# MCU098_02_BoosterPack_Connectors.net
KiCad netlist of a schematic drawn in Altium Designer
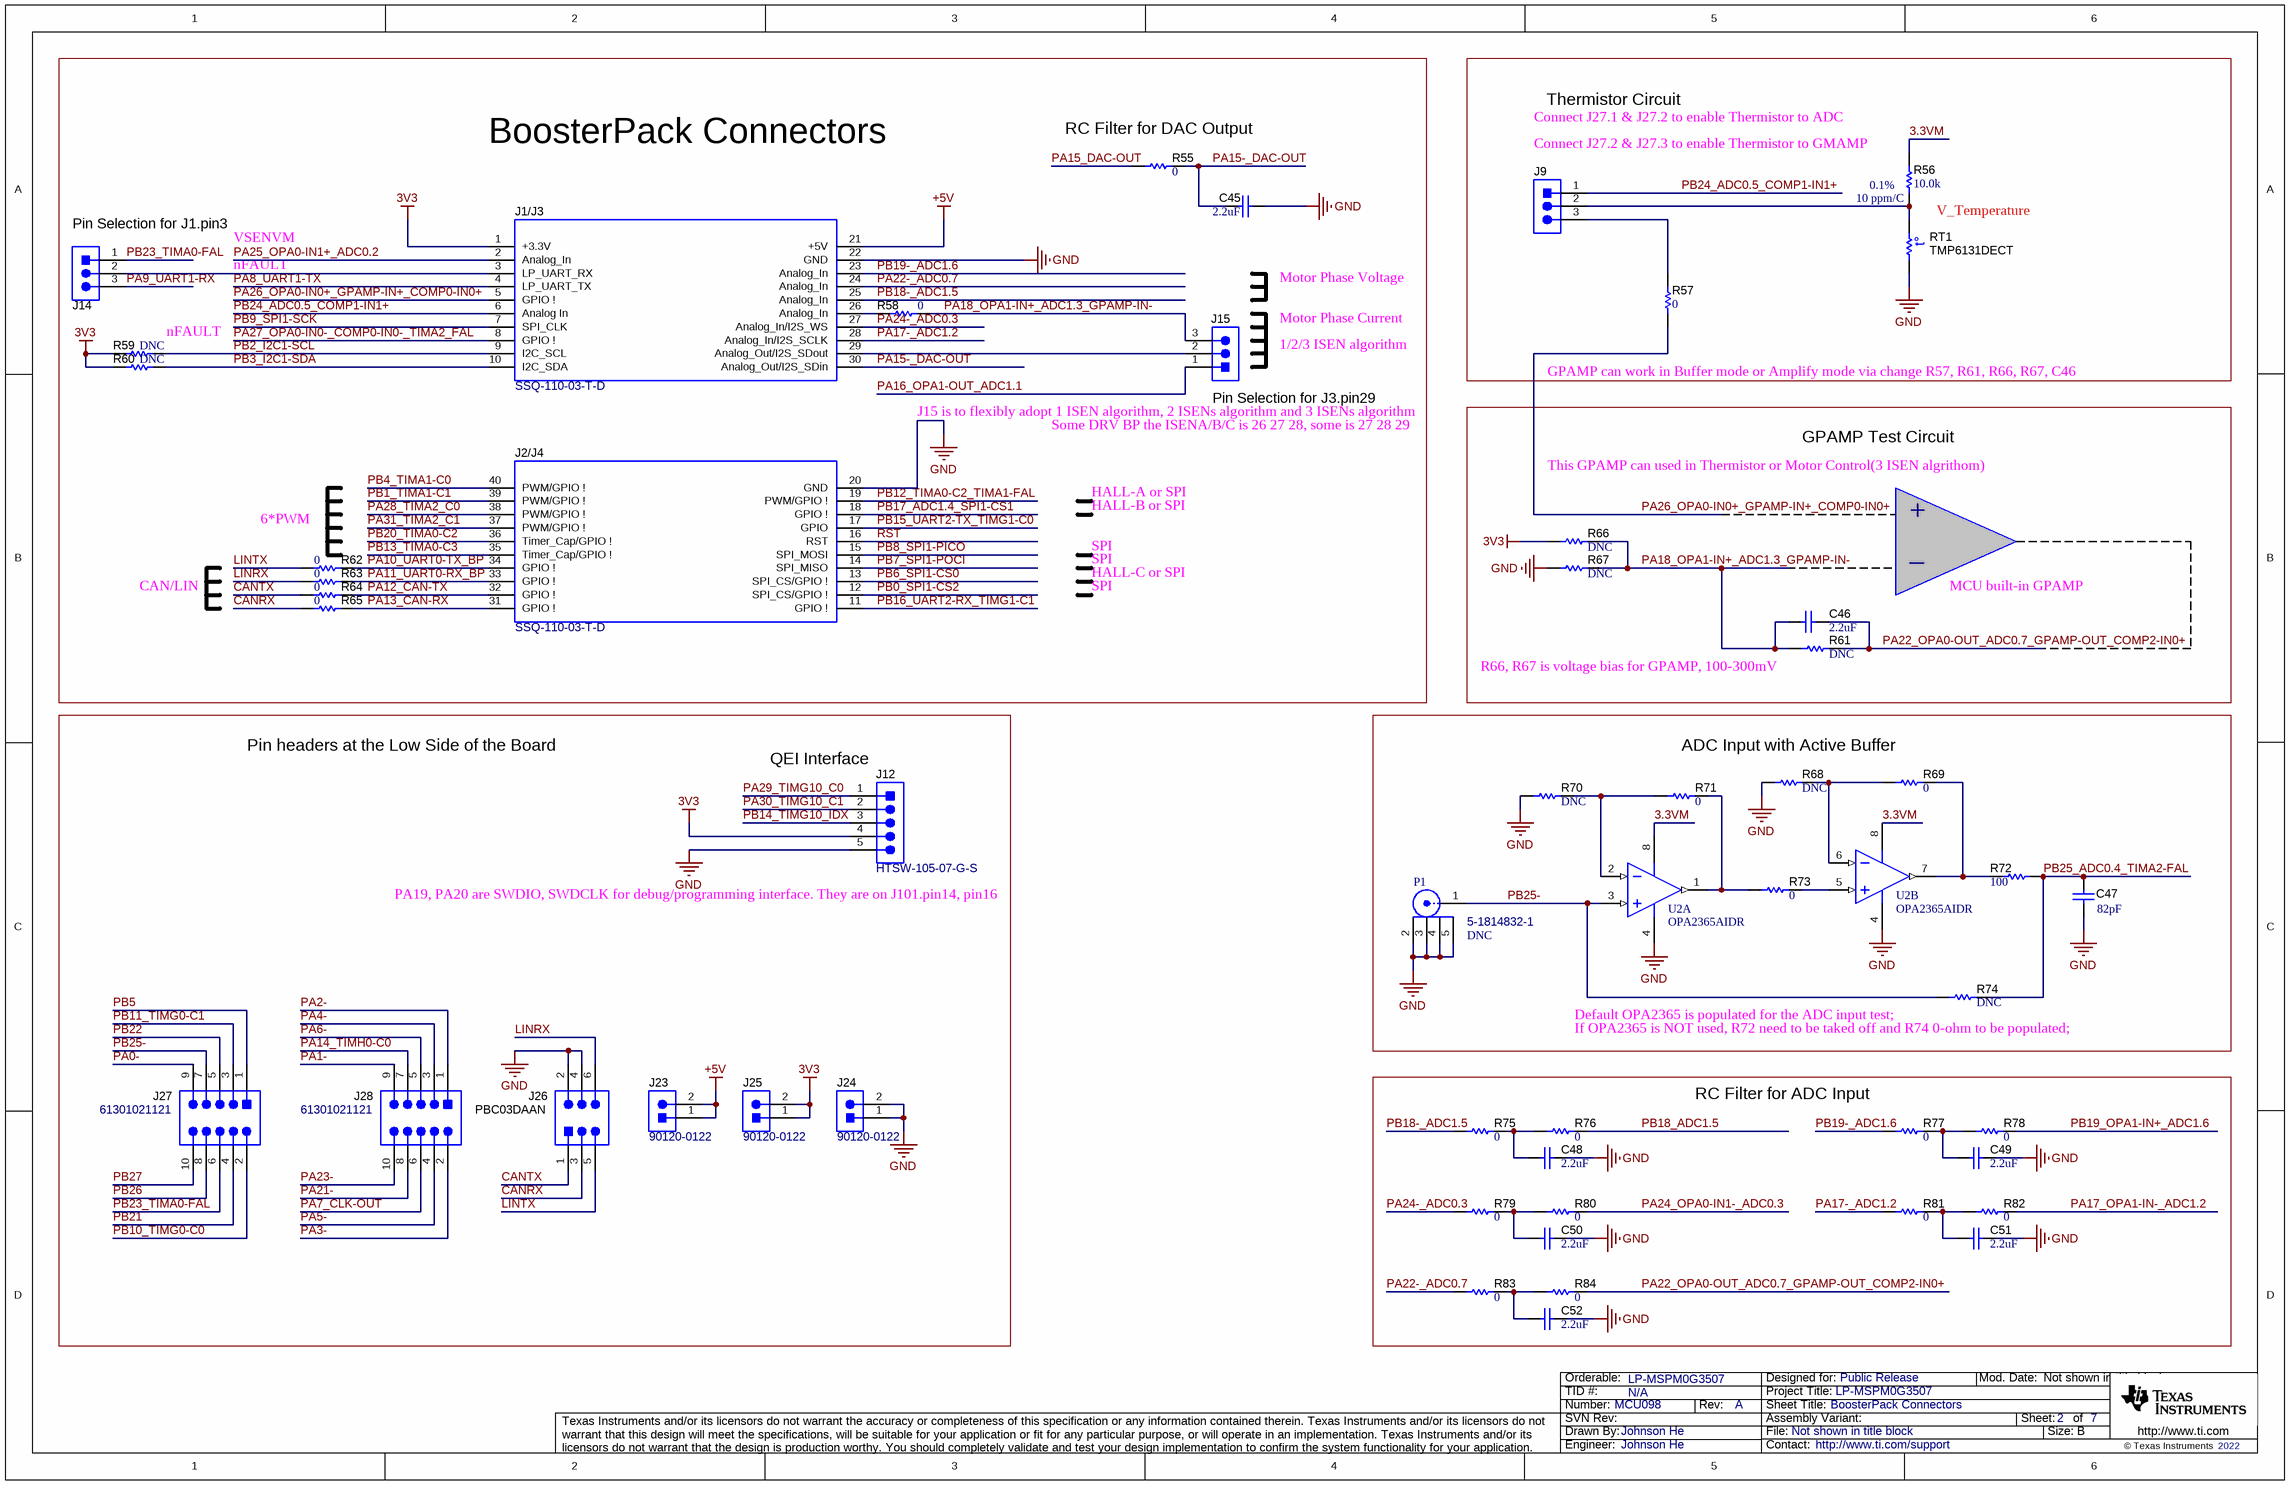
[diagram p0: MCU098_02_BoosterPack_Connectors.SchDoc]

(export (version "E")
  (design (tool "Eeschema 10.0.6"))
  (components
    (comp (ref "C45")
      (value "C0603C225K8PACTU")
      (footprint "0603")
      (description "CAP, CERM, 2.2 uF, 10 V, +/- 10%, X5R, 0603")
      (fields
        (field (name "MANUFACTURER") "Kemet")
        (field (name "VALUEDISPLAYED") "2.2uF")
        (field (name "PUBLISHER") "Texas Instruments")
      )
      (libsource (lib "Altium Vault - TI") (part "Capacitor"))
    )
    (comp (ref "C46")
      (value "C0603C225K8PACTU")
      (footprint "0603")
      (description "CAP, CERM, 2.2 uF, 10 V, +/- 10%, X5R, 0603")
      (fields
        (field (name "MANUFACTURER") "Kemet")
        (field (name "VALUEDISPLAYED") "2.2uF")
        (field (name "PUBLISHER") "Texas Instruments")
      )
      (libsource (lib "Altium Vault - TI") (part "Capacitor"))
    )
    (comp (ref "C47")
      (value "C0603C820K5GACTU")
      (footprint "0603")
      (description "CAP, CERM, 82 pF, 50 V, +/- 10%, C0G/NP0, 0603")
      (fields
        (field (name "MANUFACTURER") "Kemet")
        (field (name "VALUEDISPLAYED") "82pF")
        (field (name "PUBLISHER") "Texas Instruments")
      )
      (libsource (lib "Altium Vault - TI") (part "Capacitor"))
    )
    (comp (ref "C48")
      (value "C0603C225K8PACTU")
      (footprint "0603")
      (description "CAP, CERM, 2.2 uF, 10 V, +/- 10%, X5R, 0603")
      (fields
        (field (name "MANUFACTURER") "Kemet")
        (field (name "VALUEDISPLAYED") "2.2uF")
        (field (name "PUBLISHER") "Texas Instruments")
      )
      (libsource (lib "Altium Vault - TI") (part "Capacitor"))
    )
    (comp (ref "C49")
      (value "C0603C225K8PACTU")
      (footprint "0603")
      (description "CAP, CERM, 2.2 uF, 10 V, +/- 10%, X5R, 0603")
      (fields
        (field (name "MANUFACTURER") "Kemet")
        (field (name "VALUEDISPLAYED") "2.2uF")
        (field (name "PUBLISHER") "Texas Instruments")
      )
      (libsource (lib "Altium Vault - TI") (part "Capacitor"))
    )
    (comp (ref "C50")
      (value "C0603C225K8PACTU")
      (footprint "0603")
      (description "CAP, CERM, 2.2 uF, 10 V, +/- 10%, X5R, 0603")
      (fields
        (field (name "MANUFACTURER") "Kemet")
        (field (name "VALUEDISPLAYED") "2.2uF")
        (field (name "PUBLISHER") "Texas Instruments")
      )
      (libsource (lib "Altium Vault - TI") (part "Capacitor"))
    )
    (comp (ref "C51")
      (value "C0603C225K8PACTU")
      (footprint "0603")
      (description "CAP, CERM, 2.2 uF, 10 V, +/- 10%, X5R, 0603")
      (fields
        (field (name "MANUFACTURER") "Kemet")
        (field (name "VALUEDISPLAYED") "2.2uF")
        (field (name "PUBLISHER") "Texas Instruments")
      )
      (libsource (lib "Altium Vault - TI") (part "Capacitor"))
    )
    (comp (ref "C52")
      (value "C0603C225K8PACTU")
      (footprint "0603")
      (description "CAP, CERM, 2.2 uF, 10 V, +/- 10%, X5R, 0603")
      (fields
        (field (name "MANUFACTURER") "Kemet")
        (field (name "VALUEDISPLAYED") "2.2uF")
        (field (name "PUBLISHER") "Texas Instruments")
      )
      (libsource (lib "Altium Vault - TI") (part "Capacitor"))
    )
    (comp (ref "J1/J3")
      (value "SSQ-110-03-T-D")
      (footprint "BoosterPack_40pin_J1J3")
      (description "Receptacle, 2.54mm, 10x2, Tin, TH")
      (fields (field (name "ALTERNATE PARTNUMBER") "CRD-081413-A-G") (field (name "MANUFACTURER") "Samtec"))
      (libsource (lib "Altium Vault - TI") (part "BoosterPack_40pin_J1J3"))
    )
    (comp (ref "J2/J4")
      (value "SSQ-110-03-T-D")
      (footprint "BoosterPack_40pin_J2J4")
      (description "Receptacle, 2.54mm, 10x2, Tin, TH")
      (fields (field (name "ALTERNATE PARTNUMBER") "CRD-081413-A-G") (field (name "MANUFACTURER") "Samtec"))
      (libsource (lib "Altium Vault - TI") (part "BoosterPack_40pin_J2J4"))
    )
    (comp (ref "J9")
      (value "PEC03SAAN")
      (footprint "CONN_PEC03SAAN")
      (description "Header, 100mil, 3x1, Tin, TH")
      (fields
        (field (name "MANUFACTURER") "Sullins Connector Solutions")
        (field (name "PUBLISHER") "Texas Instruments")
      )
      (libsource (lib "") (part "Header_3x1_Launchpad_1"))
    )
    (comp (ref "J12")
      (value "HTSW-105-07-G-S")
      (footprint "Samtec_HTSW-105-07-G-S")
      (description "Header, 100mil, 5x1, Gold, TH")
      (fields (field (name "MANUFACTURER") "Samtec") (field (name "PUBLISHER") "Texas Instruments"))
      (libsource (lib "Altium Vault - TI") (part "Header_5x1"))
    )
    (comp (ref "J14")
      (value "PEC03SAAN")
      (footprint "CONN_PEC03SAAN")
      (description "Header, 100mil, 3x1, Tin, TH")
      (fields
        (field (name "MANUFACTURER") "Sullins Connector Solutions")
        (field (name "PUBLISHER") "Texas Instruments")
      )
      (libsource (lib "") (part "Header_3x1_Launchpad_1"))
    )
    (comp (ref "J15")
      (value "PEC03SAAN")
      (footprint "CONN_PEC03SAAN")
      (description "Header, 100mil, 3x1, Tin, TH")
      (fields
        (field (name "MANUFACTURER") "Sullins Connector Solutions")
        (field (name "PUBLISHER") "Texas Instruments")
      )
      (libsource (lib "Altium Vault - TI") (part "Header_3x1_Launchpad"))
    )
    (comp (ref "J23")
      (value "90120-0122")
      (footprint "CONN_90120-0122")
      (description "Header, 100mil, 2x1, Tin, TH")
      (fields (field (name "MANUFACTURER") "Molex") (field (name "PUBLISHER") "Texas Instruments"))
      (libsource (lib "Altium Vault - TI") (part "Header_2x1"))
    )
    (comp (ref "J24")
      (value "90120-0122")
      (footprint "CONN_90120-0122")
      (description "Header, 100mil, 2x1, Tin, TH")
      (fields (field (name "MANUFACTURER") "Molex") (field (name "PUBLISHER") "Texas Instruments"))
      (libsource (lib "Altium Vault - TI") (part "Header_2x1"))
    )
    (comp (ref "J25")
      (value "90120-0122")
      (footprint "CONN_90120-0122")
      (description "Header, 100mil, 2x1, Tin, TH")
      (fields (field (name "MANUFACTURER") "Molex") (field (name "PUBLISHER") "Texas Instruments"))
      (libsource (lib "Altium Vault - TI") (part "Header_2x1"))
    )
    (comp (ref "J26")
      (value "PBC03DAAN")
      (footprint "Sullins_PBC03DAAN")
      (description "Header, 100mil, 3x2, Gold, TH")
      (fields (field (name "MANUFACTURER") "Sullins Connector Solutions"))
      (libsource (lib "Altium Vault - TI") (part "Header_3x2"))
    )
    (comp (ref "J27")
      (value "61301021121")
      (footprint "WURTH_61301021121")
      (description "Header, 2.54 mm, 5x2, Gold, TH")
      (fields (field (name "MANUFACTURER") "Wurth Elektronik"))
      (libsource (lib "Altium Vault - TI") (part "Header_5x2"))
    )
    (comp (ref "J28")
      (value "61301021121")
      (footprint "WURTH_61301021121")
      (description "Header, 2.54 mm, 5x2, Gold, TH")
      (fields (field (name "MANUFACTURER") "Wurth Elektronik"))
      (libsource (lib "Altium Vault - TI") (part "Header_5x2"))
    )
    (comp (ref "P1")
      (value "5-1814832-1")
      (footprint "TE_5-1814832-1")
      (description "SMA Straight PCB Socket Die Cast, 50 Ohm, TH")
      (fields
        (field (name "MANUFACTURER") "TE Connectivity")
        (field (name "VALUEDISPLAYED") "DNC")
        (field (name "PUBLISHER") "Texas Instruments")
      )
      (libsource (lib "Altium Vault - TI") (part "SMA_Contact1_GND2345"))
    )
    (comp (ref "R55")
      (value "RC0603JR-070RL")
      (footprint "0603")
      (description "RES, 0, 5%, 0.1 W, 0603")
      (fields (field (name "MANUFACTURER") "Yageo") (field (name "VALUEDISPLAYED") "0"))
      (libsource (lib "Altium Vault - TI") (part "Resistor"))
    )
    (comp (ref "R56")
      (value "ERA3ARB103V")
      (footprint "ERA3A")
      (description "RES, 10.0 k, 0.1%, 0.1 W, AEC-Q200 Grade 0, 1.6x0.8mm")
      (fields
        (field (name "TOLERANCE_%") "0.1%")
        (field (name "MANUFACTURER") "Panasonic")
        (field (name "TEMPCO") "10 ppm/C")
        (field (name "VALUEDISPLAYED") "10.0k")
      )
      (libsource (lib "Altium Vault - TI") (part "Resistor"))
    )
    (comp (ref "R57")
      (value "RC0603JR-070RL")
      (footprint "0603")
      (description "RES, 0, 5%, 0.1 W, 0603")
      (fields (field (name "MANUFACTURER") "Yageo") (field (name "VALUEDISPLAYED") "0"))
      (libsource (lib "Altium Vault - TI") (part "Resistor"))
    )
    (comp (ref "R58")
      (value "RC0603JR-070RL")
      (footprint "0603")
      (description "RES, 0, 5%, 0.1 W, 0603")
      (fields (field (name "MANUFACTURER") "Yageo") (field (name "VALUEDISPLAYED") "0"))
      (libsource (lib "Altium Vault - TI") (part "Resistor"))
    )
    (comp (ref "R59")
      (value "CRCW04024K70JNED")
      (footprint "0402")
      (description "RES, 4.7 k, 5%, 0.063 W, AEC-Q200 Grade 0, 0402")
      (fields (field (name "MANUFACTURER") "Vishay-Dale") (field (name "VALUEDISPLAYED") "DNC"))
      (libsource (lib "Altium Vault - TI") (part "Resistor"))
    )
    (comp (ref "R60")
      (value "CRCW04024K70JNED")
      (footprint "0402")
      (description "RES, 4.7 k, 5%, 0.063 W, AEC-Q200 Grade 0, 0402")
      (fields (field (name "MANUFACTURER") "Vishay-Dale") (field (name "VALUEDISPLAYED") "DNC"))
      (libsource (lib "Altium Vault - TI") (part "Resistor"))
    )
    (comp (ref "R61")
      (value "RC0603JR-070RL")
      (footprint "0603")
      (description "RES, 0, 5%, 0.1 W, 0603")
      (fields (field (name "MANUFACTURER") "Yageo") (field (name "VALUEDISPLAYED") "DNC"))
      (libsource (lib "Altium Vault - TI") (part "Resistor"))
    )
    (comp (ref "R62")
      (value "RC0603JR-070RL")
      (footprint "0603")
      (description "RES, 0, 5%, 0.1 W, 0603")
      (fields (field (name "MANUFACTURER") "Yageo") (field (name "VALUEDISPLAYED") "0"))
      (libsource (lib "Altium Vault - TI") (part "Resistor"))
    )
    (comp (ref "R63")
      (value "RC0603JR-070RL")
      (footprint "0603")
      (description "RES, 0, 5%, 0.1 W, 0603")
      (fields (field (name "MANUFACTURER") "Yageo") (field (name "VALUEDISPLAYED") "0"))
      (libsource (lib "Altium Vault - TI") (part "Resistor"))
    )
    (comp (ref "R64")
      (value "RC0603JR-070RL")
      (footprint "0603")
      (description "RES, 0, 5%, 0.1 W, 0603")
      (fields (field (name "MANUFACTURER") "Yageo") (field (name "VALUEDISPLAYED") "0"))
      (libsource (lib "Altium Vault - TI") (part "Resistor"))
    )
    (comp (ref "R65")
      (value "RC0603JR-070RL")
      (footprint "0603")
      (description "RES, 0, 5%, 0.1 W, 0603")
      (fields (field (name "MANUFACTURER") "Yageo") (field (name "VALUEDISPLAYED") "0"))
      (libsource (lib "Altium Vault - TI") (part "Resistor"))
    )
    (comp (ref "R66")
      (value "RC0603JR-070RL")
      (footprint "0603")
      (description "RES, 0, 5%, 0.1 W, 0603")
      (fields (field (name "MANUFACTURER") "Yageo") (field (name "VALUEDISPLAYED") "DNC"))
      (libsource (lib "Altium Vault - TI") (part "Resistor"))
    )
    (comp (ref "R67")
      (value "RC0603JR-070RL")
      (footprint "0603")
      (description "RES, 0, 5%, 0.1 W, 0603")
      (fields (field (name "MANUFACTURER") "Yageo") (field (name "VALUEDISPLAYED") "DNC"))
      (libsource (lib "Altium Vault - TI") (part "Resistor"))
    )
    (comp (ref "R68")
      (value "RC0603JR-070RL")
      (footprint "0603")
      (description "RES, 0, 5%, 0.1 W, 0603")
      (fields (field (name "MANUFACTURER") "Yageo") (field (name "VALUEDISPLAYED") "DNC"))
      (libsource (lib "Altium Vault - TI") (part "Resistor"))
    )
    (comp (ref "R69")
      (value "RC0603JR-070RL")
      (footprint "0603")
      (description "RES, 0, 5%, 0.1 W, 0603")
      (fields (field (name "MANUFACTURER") "Yageo") (field (name "VALUEDISPLAYED") "0"))
      (libsource (lib "Altium Vault - TI") (part "Resistor"))
    )
    (comp (ref "R70")
      (value "RC0603JR-070RL")
      (footprint "0603")
      (description "RES, 0, 5%, 0.1 W, 0603")
      (fields (field (name "MANUFACTURER") "Yageo") (field (name "VALUEDISPLAYED") "DNC"))
      (libsource (lib "Altium Vault - TI") (part "Resistor"))
    )
    (comp (ref "R71")
      (value "RC0603JR-070RL")
      (footprint "0603")
      (description "RES, 0, 5%, 0.1 W, 0603")
      (fields (field (name "MANUFACTURER") "Yageo") (field (name "VALUEDISPLAYED") "0"))
      (libsource (lib "Altium Vault - TI") (part "Resistor"))
    )
    (comp (ref "R72")
      (value "RC0603FR-07100RL")
      (footprint "0603")
      (description "RES, 100, 1%, 0.1 W, 0603")
      (fields (field (name "MANUFACTURER") "Yageo") (field (name "VALUEDISPLAYED") "100"))
      (libsource (lib "Altium Vault - TI") (part "Resistor"))
    )
    (comp (ref "R73")
      (value "RC0603JR-070RL")
      (footprint "0603")
      (description "RES, 0, 5%, 0.1 W, 0603")
      (fields (field (name "MANUFACTURER") "Yageo") (field (name "VALUEDISPLAYED") "0"))
      (libsource (lib "Altium Vault - TI") (part "Resistor"))
    )
    (comp (ref "R74")
      (value "RC0603JR-070RL")
      (footprint "0603")
      (description "RES, 0, 5%, 0.1 W, 0603")
      (fields (field (name "MANUFACTURER") "Yageo") (field (name "VALUEDISPLAYED") "DNC"))
      (libsource (lib "Altium Vault - TI") (part "Resistor"))
    )
    (comp (ref "R75")
      (value "RC0603JR-070RL")
      (footprint "0603")
      (description "RES, 0, 5%, 0.1 W, 0603")
      (fields (field (name "MANUFACTURER") "Yageo") (field (name "VALUEDISPLAYED") "0"))
      (libsource (lib "Altium Vault - TI") (part "Resistor"))
    )
    (comp (ref "R76")
      (value "RC0603JR-070RL")
      (footprint "0603")
      (description "RES, 0, 5%, 0.1 W, 0603")
      (fields (field (name "MANUFACTURER") "Yageo") (field (name "VALUEDISPLAYED") "0"))
      (libsource (lib "Altium Vault - TI") (part "Resistor"))
    )
    (comp (ref "R77")
      (value "RC0603JR-070RL")
      (footprint "0603")
      (description "RES, 0, 5%, 0.1 W, 0603")
      (fields (field (name "MANUFACTURER") "Yageo") (field (name "VALUEDISPLAYED") "0"))
      (libsource (lib "Altium Vault - TI") (part "Resistor"))
    )
    (comp (ref "R78")
      (value "RC0603JR-070RL")
      (footprint "0603")
      (description "RES, 0, 5%, 0.1 W, 0603")
      (fields (field (name "MANUFACTURER") "Yageo") (field (name "VALUEDISPLAYED") "0"))
      (libsource (lib "Altium Vault - TI") (part "Resistor"))
    )
    (comp (ref "R79")
      (value "RC0603JR-070RL")
      (footprint "0603")
      (description "RES, 0, 5%, 0.1 W, 0603")
      (fields (field (name "MANUFACTURER") "Yageo") (field (name "VALUEDISPLAYED") "0"))
      (libsource (lib "Altium Vault - TI") (part "Resistor"))
    )
    (comp (ref "R80")
      (value "RC0603JR-070RL")
      (footprint "0603")
      (description "RES, 0, 5%, 0.1 W, 0603")
      (fields (field (name "MANUFACTURER") "Yageo") (field (name "VALUEDISPLAYED") "0"))
      (libsource (lib "Altium Vault - TI") (part "Resistor"))
    )
    (comp (ref "R81")
      (value "RC0603JR-070RL")
      (footprint "0603")
      (description "RES, 0, 5%, 0.1 W, 0603")
      (fields (field (name "MANUFACTURER") "Yageo") (field (name "VALUEDISPLAYED") "0"))
      (libsource (lib "Altium Vault - TI") (part "Resistor"))
    )
    (comp (ref "R82")
      (value "RC0603JR-070RL")
      (footprint "0603")
      (description "RES, 0, 5%, 0.1 W, 0603")
      (fields (field (name "MANUFACTURER") "Yageo") (field (name "VALUEDISPLAYED") "0"))
      (libsource (lib "Altium Vault - TI") (part "Resistor"))
    )
    (comp (ref "R83")
      (value "RC0603JR-070RL")
      (footprint "0603")
      (description "RES, 0, 5%, 0.1 W, 0603")
      (fields (field (name "MANUFACTURER") "Yageo") (field (name "VALUEDISPLAYED") "0"))
      (libsource (lib "Altium Vault - TI") (part "Resistor"))
    )
    (comp (ref "R84")
      (value "RC0603JR-070RL")
      (footprint "0603")
      (description "RES, 0, 5%, 0.1 W, 0603")
      (fields (field (name "MANUFACTURER") "Yageo") (field (name "VALUEDISPLAYED") "0"))
      (libsource (lib "Altium Vault - TI") (part "Resistor"))
    )
    (comp (ref "RT1")
      (value "TMP6131DECT")
      (footprint "DEC0002A")
      (description "Thermistor, DEC0002A (X1SON-2)")
      (fields
        (field (name "ALTERNATE PARTNUMBER") "TMP6131DECR")
        (field (name "PARTNUMBER") "TMP6131DECT")
        (field (name "MANUFACTURER") "Texas Instruments")
      )
      (libsource (lib "Altium Vault - TI") (part "Thermistor"))
    )
    (comp (ref "U2")
      (value "OPA2365AIDR")
      (footprint "D0008A_L")
      (fields (field (name "MANUFACTURER") "Texas Instruments") (field (name "PARTNUMBER") "OPA2365AIDR"))
      (libsource (lib "Altium Vault - TI") (part "TI-OPA2365D8"))
    )
  )
  (nets
    (net (code "1") (name "+5V") (class "Default")
      (node (ref "J1/J3") (pin "21") (pinfunction "+5V_21") (pintype "power_in"))
      (node (ref "J23") (pin "1") (pinfunction "1_1") (pintype "passive"))
      (node (ref "J23") (pin "2") (pinfunction "2_2") (pintype "passive"))
    )
    (net (code "2") (name "/3.3VM") (class "Default")
      (node (ref "R56") (pin "2") (pinfunction "2_2") (pintype "passive"))
      (node (ref "U2") (pin "8") (pinfunction "V+_8") (pintype "power_in"))
    )
    (net (code "3") (name "/CANRX") (class "Default")
      (node (ref "J26") (pin "3") (pinfunction "3_3") (pintype "passive"))
      (node (ref "R65") (pin "1") (pinfunction "1_1") (pintype "passive"))
    )
    (net (code "4") (name "/CANTX") (class "Default")
      (node (ref "J26") (pin "1") (pinfunction "1_1") (pintype "passive"))
      (node (ref "R64") (pin "1") (pinfunction "1_1") (pintype "passive"))
    )
    (net (code "5") (name "/LINRX") (class "Default")
      (node (ref "J26") (pin "6") (pinfunction "6_6") (pintype "passive"))
      (node (ref "R63") (pin "1") (pinfunction "1_1") (pintype "passive"))
    )
    (net (code "6") (name "/LINTX") (class "Default")
      (node (ref "J26") (pin "5") (pinfunction "5_5") (pintype "passive"))
      (node (ref "R62") (pin "1") (pinfunction "1_1") (pintype "passive"))
    )
    (net (code "7") (name "/PA0-") (class "Default")
      (node (ref "J27") (pin "9") (pinfunction "9_9") (pintype "passive"))
    )
    (net (code "8") (name "/PA1-") (class "Default")
      (node (ref "J28") (pin "9") (pinfunction "9_9") (pintype "passive"))
    )
    (net (code "9") (name "/PA2-") (class "Default")
      (node (ref "J28") (pin "1") (pinfunction "1_1") (pintype "passive"))
    )
    (net (code "10") (name "/PA3-") (class "Default")
      (node (ref "J28") (pin "2") (pinfunction "2_2") (pintype "passive"))
    )
    (net (code "11") (name "/PA4-") (class "Default")
      (node (ref "J28") (pin "3") (pinfunction "3_3") (pintype "passive"))
    )
    (net (code "12") (name "/PA5-") (class "Default")
      (node (ref "J28") (pin "4") (pinfunction "4_4") (pintype "passive"))
    )
    (net (code "13") (name "/PA6-") (class "Default")
      (node (ref "J28") (pin "5") (pinfunction "5_5") (pintype "passive"))
    )
    (net (code "14") (name "/PA7_CLK-OUT") (class "Default")
      (node (ref "J28") (pin "6") (pinfunction "6_6") (pintype "passive"))
    )
    (net (code "15") (name "/PA8_UART1-TX") (class "Default")
      (node (ref "J1/J3") (pin "4") (pinfunction "LP_UART_TX_4") (pintype "passive"))
    )
    (net (code "16") (name "/PA9_UART1-RX") (class "Default")
      (node (ref "J14") (pin "3") (pinfunction "3_3") (pintype "passive"))
    )
    (net (code "17") (name "/PA10_UART0-TX_BP") (class "Default")
      (node (ref "J2/J4") (pin "34") (pinfunction "GPIO_!_34") (pintype "passive"))
      (node (ref "R62") (pin "2") (pinfunction "2_2") (pintype "passive"))
    )
    (net (code "18") (name "/PA11_UART0-RX_BP") (class "Default")
      (node (ref "J2/J4") (pin "33") (pinfunction "GPIO_!_33") (pintype "passive"))
      (node (ref "R63") (pin "2") (pinfunction "2_2") (pintype "passive"))
    )
    (net (code "19") (name "/PA12_CAN-TX") (class "Default")
      (node (ref "J2/J4") (pin "32") (pinfunction "GPIO_!_32") (pintype "passive"))
      (node (ref "R64") (pin "2") (pinfunction "2_2") (pintype "passive"))
    )
    (net (code "20") (name "/PA13_CAN-RX") (class "Default")
      (node (ref "J2/J4") (pin "31") (pinfunction "GPIO_!_31") (pintype "passive"))
      (node (ref "R65") (pin "2") (pinfunction "2_2") (pintype "passive"))
    )
    (net (code "21") (name "/PA14_TIMH0-C0") (class "Default")
      (node (ref "J28") (pin "7") (pinfunction "7_7") (pintype "passive"))
    )
    (net (code "22") (name "/PA15-_DAC-OUT") (class "Default")
      (node (ref "C45") (pin "1") (pinfunction "1_1") (pintype "passive"))
      (node (ref "J1/J3") (pin "30") (pinfunction "Analog_Out/I2S_SDin_30") (pintype "passive"))
      (node (ref "R55") (pin "2") (pinfunction "2_2") (pintype "passive"))
    )
    (net (code "23") (name "/PA15_DAC-OUT") (class "Default")
      (node (ref "R55") (pin "1") (pinfunction "1_1") (pintype "passive"))
    )
    (net (code "24") (name "/PA16_OPA1-OUT_ADC1.1") (class "Default")
      (node (ref "J15") (pin "1") (pinfunction "1_1") (pintype "passive"))
    )
    (net (code "25") (name "/PA17-_ADC1.2") (class "Default")
      (node (ref "J1/J3") (pin "28") (pinfunction "Analog_In/I2S_SCLK_28") (pintype "passive"))
      (node (ref "R81") (pin "1") (pinfunction "1_1") (pintype "passive"))
    )
    (net (code "26") (name "/PA17_OPA1-IN-_ADC1.2") (class "Default")
      (node (ref "R82") (pin "2") (pinfunction "2_2") (pintype "passive"))
    )
    (net (code "27") (name "/PA18_OPA1-IN+_ADC1.3_GPAMP-IN-") (class "Default")
      (node (ref "C46") (pin "1") (pinfunction "1_1") (pintype "passive"))
      (node (ref "J15") (pin "3") (pinfunction "3_3") (pintype "passive"))
      (node (ref "R58") (pin "2") (pinfunction "2_2") (pintype "passive"))
      (node (ref "R61") (pin "1") (pinfunction "1_1") (pintype "passive"))
      (node (ref "R66") (pin "2") (pinfunction "2_2") (pintype "passive"))
      (node (ref "R67") (pin "2") (pinfunction "2_2") (pintype "passive"))
    )
    (net (code "28") (name "/PA21-") (class "Default")
      (node (ref "J28") (pin "8") (pinfunction "8_8") (pintype "passive"))
    )
    (net (code "29") (name "/PA22-_ADC0.7") (class "Default")
      (node (ref "J1/J3") (pin "24") (pinfunction "Analog_In_24") (pintype "passive"))
      (node (ref "R83") (pin "1") (pinfunction "1_1") (pintype "passive"))
    )
    (net (code "30") (name "/PA22_OPA0-OUT_ADC0.7_GPAMP-OUT_COMP2-IN0+") (class "Default")
      (node (ref "C46") (pin "2") (pinfunction "2_2") (pintype "passive"))
      (node (ref "R61") (pin "2") (pinfunction "2_2") (pintype "passive"))
      (node (ref "R84") (pin "2") (pinfunction "2_2") (pintype "passive"))
    )
    (net (code "31") (name "/PA23-") (class "Default")
      (node (ref "J28") (pin "10") (pinfunction "10_10") (pintype "passive"))
    )
    (net (code "32") (name "/PA24-_ADC0.3") (class "Default")
      (node (ref "J1/J3") (pin "27") (pinfunction "Analog_In/I2S_WS_27") (pintype "passive"))
      (node (ref "R79") (pin "1") (pinfunction "1_1") (pintype "passive"))
    )
    (net (code "33") (name "/PA24_OPA0-IN1-_ADC0.3") (class "Default")
      (node (ref "R80") (pin "2") (pinfunction "2_2") (pintype "passive"))
    )
    (net (code "34") (name "/PA25_OPA0-IN1+_ADC0.2") (class "Default")
      (node (ref "J1/J3") (pin "2") (pinfunction "Analog_In_2") (pintype "passive"))
    )
    (net (code "35") (name "/PA26_OPA0-IN0+_GPAMP-IN+_COMP0-IN0+") (class "Default")
      (node (ref "J1/J3") (pin "5") (pinfunction "GPIO_!_5") (pintype "passive"))
      (node (ref "R57") (pin "1") (pinfunction "1_1") (pintype "passive"))
    )
    (net (code "36") (name "/PA27_OPA0-IN0-_COMP0-IN0-_TIMA2_FAL") (class "Default")
      (node (ref "J1/J3") (pin "8") (pinfunction "GPIO_!_8") (pintype "passive"))
    )
    (net (code "37") (name "/PA28_TIMA2_C0") (class "Default")
      (node (ref "J2/J4") (pin "38") (pinfunction "PWM/GPIO_!_38") (pintype "passive"))
    )
    (net (code "38") (name "/PA29_TIMG10_C0") (class "Default")
      (node (ref "J12") (pin "1") (pinfunction "1_1") (pintype "passive"))
    )
    (net (code "39") (name "/PA30_TIMG10_C1") (class "Default")
      (node (ref "J12") (pin "2") (pinfunction "2_2") (pintype "passive"))
    )
    (net (code "40") (name "/PA31_TIMA2_C1") (class "Default")
      (node (ref "J2/J4") (pin "37") (pinfunction "PWM/GPIO_!_37") (pintype "passive"))
    )
    (net (code "41") (name "/PB0_SPI1-CS2") (class "Default")
      (node (ref "J2/J4") (pin "12") (pinfunction "SPI_CS/GPIO_!_12") (pintype "passive"))
    )
    (net (code "42") (name "/PB1_TIMA1-C1") (class "Default")
      (node (ref "J2/J4") (pin "39") (pinfunction "PWM/GPIO_!_39") (pintype "passive"))
    )
    (net (code "43") (name "/PB2_I2C1-SCL") (class "Default")
      (node (ref "J1/J3") (pin "9") (pinfunction "I2C_SCL_9") (pintype "passive"))
      (node (ref "R59") (pin "2") (pinfunction "2_2") (pintype "passive"))
    )
    (net (code "44") (name "/PB3_I2C1-SDA") (class "Default")
      (node (ref "J1/J3") (pin "10") (pinfunction "I2C_SDA_10") (pintype "passive"))
      (node (ref "R60") (pin "2") (pinfunction "2_2") (pintype "passive"))
    )
    (net (code "45") (name "/PB4_TIMA1-C0") (class "Default")
      (node (ref "J2/J4") (pin "40") (pinfunction "PWM/GPIO_!_40") (pintype "passive"))
    )
    (net (code "46") (name "/PB5") (class "Default")
      (node (ref "J27") (pin "1") (pinfunction "1_1") (pintype "passive"))
    )
    (net (code "47") (name "/PB6_SPI1-CS0") (class "Default")
      (node (ref "J2/J4") (pin "13") (pinfunction "SPI_CS/GPIO_!_13") (pintype "passive"))
    )
    (net (code "48") (name "/PB7_SPI1-POCI") (class "Default")
      (node (ref "J2/J4") (pin "14") (pinfunction "SPI_MISO_14") (pintype "passive"))
    )
    (net (code "49") (name "/PB8_SPI1-PICO") (class "Default")
      (node (ref "J2/J4") (pin "15") (pinfunction "SPI_MOSI_15") (pintype "passive"))
    )
    (net (code "50") (name "/PB9_SPI1-SCK") (class "Default")
      (node (ref "J1/J3") (pin "7") (pinfunction "SPI_CLK_7") (pintype "passive"))
    )
    (net (code "51") (name "/PB10_TIMG0-C0") (class "Default")
      (node (ref "J27") (pin "2") (pinfunction "2_2") (pintype "passive"))
    )
    (net (code "52") (name "/PB11_TIMG0-C1") (class "Default")
      (node (ref "J27") (pin "3") (pinfunction "3_3") (pintype "passive"))
    )
    (net (code "53") (name "/PB12_TIMA0-C2_TIMA1-FAL") (class "Default")
      (node (ref "J2/J4") (pin "19") (pinfunction "PWM/GPIO_!_19") (pintype "passive"))
    )
    (net (code "54") (name "/PB13_TIMA0-C3") (class "Default")
      (node (ref "J2/J4") (pin "35") (pinfunction "Timer_Cap/GPIO_!_35") (pintype "passive"))
    )
    (net (code "55") (name "/PB14_TIMG10_IDX") (class "Default")
      (node (ref "J12") (pin "3") (pinfunction "3_3") (pintype "passive"))
    )
    (net (code "56") (name "/PB15_UART2-TX_TIMG1-C0") (class "Default")
      (node (ref "J2/J4") (pin "17") (pinfunction "GPIO_17") (pintype "passive"))
    )
    (net (code "57") (name "/PB16_UART2-RX_TIMG1-C1") (class "Default")
      (node (ref "J2/J4") (pin "11") (pinfunction "GPIO_!_11") (pintype "passive"))
    )
    (net (code "58") (name "/PB17_ADC1.4_SPI1-CS1") (class "Default")
      (node (ref "J2/J4") (pin "18") (pinfunction "GPIO_!_18") (pintype "passive"))
    )
    (net (code "59") (name "/PB18-_ADC1.5") (class "Default")
      (node (ref "J1/J3") (pin "25") (pinfunction "Analog_In_25") (pintype "passive"))
      (node (ref "R75") (pin "1") (pinfunction "1_1") (pintype "passive"))
    )
    (net (code "60") (name "/PB18_ADC1.5") (class "Default")
      (node (ref "R76") (pin "2") (pinfunction "2_2") (pintype "passive"))
    )
    (net (code "61") (name "/PB19-_ADC1.6") (class "Default")
      (node (ref "J1/J3") (pin "23") (pinfunction "Analog_In_23") (pintype "passive"))
      (node (ref "R77") (pin "1") (pinfunction "1_1") (pintype "passive"))
    )
    (net (code "62") (name "/PB19_OPA1-IN+_ADC1.6") (class "Default")
      (node (ref "R78") (pin "2") (pinfunction "2_2") (pintype "passive"))
    )
    (net (code "63") (name "/PB20_TIMA0-C2") (class "Default")
      (node (ref "J2/J4") (pin "36") (pinfunction "Timer_Cap/GPIO_!_36") (pintype "passive"))
    )
    (net (code "64") (name "/PB21") (class "Default")
      (node (ref "J27") (pin "4") (pinfunction "4_4") (pintype "passive"))
    )
    (net (code "65") (name "/PB22") (class "Default")
      (node (ref "J27") (pin "5") (pinfunction "5_5") (pintype "passive"))
    )
    (net (code "66") (name "/PB23_TIMA0-FAL") (class "Default")
      (node (ref "J14") (pin "1") (pinfunction "1_1") (pintype "passive"))
      (node (ref "J27") (pin "6") (pinfunction "6_6") (pintype "passive"))
    )
    (net (code "67") (name "/PB24_ADC0.5_COMP1-IN1+") (class "Default")
      (node (ref "J1/J3") (pin "6") (pinfunction "Analog_In_6") (pintype "passive"))
      (node (ref "J9") (pin "1") (pinfunction "1_1") (pintype "passive"))
    )
    (net (code "68") (name "/PB25-") (class "Default")
      (node (ref "J27") (pin "7") (pinfunction "7_7") (pintype "passive"))
      (node (ref "P1") (pin "1") (pinfunction "1_1") (pintype "passive"))
      (node (ref "R74") (pin "1") (pinfunction "1_1") (pintype "passive"))
      (node (ref "U2") (pin "3") (pinfunction "IN_A+_3") (pintype "input"))
    )
    (net (code "69") (name "/PB25_ADC0.4_TIMA2-FAL") (class "Default")
      (node (ref "C47") (pin "1") (pinfunction "1_1") (pintype "passive"))
      (node (ref "R72") (pin "2") (pinfunction "2_2") (pintype "passive"))
      (node (ref "R74") (pin "2") (pinfunction "2_2") (pintype "passive"))
    )
    (net (code "70") (name "/PB26") (class "Default")
      (node (ref "J27") (pin "8") (pinfunction "8_8") (pintype "passive"))
    )
    (net (code "71") (name "/PB27") (class "Default")
      (node (ref "J27") (pin "10") (pinfunction "10_10") (pintype "passive"))
    )
    (net (code "72") (name "/~{RST}") (class "Default")
      (node (ref "J2/J4") (pin "16") (pinfunction "RST_16") (pintype "passive"))
    )
    (net (code "73") (name "3V3") (class "Default")
      (node (ref "J1/J3") (pin "1") (pinfunction "+3.3V_1") (pintype "power_in"))
      (node (ref "J12") (pin "4") (pinfunction "4_4") (pintype "passive"))
      (node (ref "J25") (pin "1") (pinfunction "1_1") (pintype "passive"))
      (node (ref "J25") (pin "2") (pinfunction "2_2") (pintype "passive"))
      (node (ref "R59") (pin "1") (pinfunction "1_1") (pintype "passive"))
      (node (ref "R60") (pin "1") (pinfunction "1_1") (pintype "passive"))
      (node (ref "R66") (pin "1") (pinfunction "1_1") (pintype "passive"))
    )
    (net (code "74") (name "GND") (class "Default")
      (node (ref "C45") (pin "2") (pinfunction "2_2") (pintype "passive"))
      (node (ref "C47") (pin "2") (pinfunction "2_2") (pintype "passive"))
      (node (ref "C48") (pin "2") (pinfunction "2_2") (pintype "passive"))
      (node (ref "C49") (pin "2") (pinfunction "2_2") (pintype "passive"))
      (node (ref "C50") (pin "2") (pinfunction "2_2") (pintype "passive"))
      (node (ref "C51") (pin "2") (pinfunction "2_2") (pintype "passive"))
      (node (ref "C52") (pin "2") (pinfunction "2_2") (pintype "passive"))
      (node (ref "J1/J3") (pin "22") (pinfunction "GND_22") (pintype "power_in"))
      (node (ref "J12") (pin "5") (pinfunction "5_5") (pintype "passive"))
      (node (ref "J2/J4") (pin "20") (pinfunction "GND_20") (pintype "power_in"))
      (node (ref "J24") (pin "1") (pinfunction "1_1") (pintype "passive"))
      (node (ref "J24") (pin "2") (pinfunction "2_2") (pintype "passive"))
      (node (ref "J26") (pin "2") (pinfunction "2_2") (pintype "passive"))
      (node (ref "J26") (pin "4") (pinfunction "4_4") (pintype "passive"))
      (node (ref "P1") (pin "2") (pinfunction "2_2") (pintype "passive"))
      (node (ref "P1") (pin "3") (pinfunction "3_3") (pintype "passive"))
      (node (ref "P1") (pin "4") (pinfunction "4_4") (pintype "passive"))
      (node (ref "P1") (pin "5") (pinfunction "5_5") (pintype "passive"))
      (node (ref "R67") (pin "1") (pinfunction "1_1") (pintype "passive"))
      (node (ref "R68") (pin "1") (pinfunction "1_1") (pintype "passive"))
      (node (ref "R70") (pin "1") (pinfunction "1_1") (pintype "passive"))
      (node (ref "RT1") (pin "1") (pinfunction "1_1") (pintype "passive"))
      (node (ref "U2") (pin "4") (pinfunction "V-_4") (pintype "power_in"))
    )
    (net (code "75") (name "Net-(C48-Pad1)") (class "Default")
      (node (ref "C48") (pin "1") (pinfunction "1_1") (pintype "passive"))
      (node (ref "R75") (pin "2") (pinfunction "2_2") (pintype "passive"))
      (node (ref "R76") (pin "1") (pinfunction "1_1") (pintype "passive"))
    )
    (net (code "76") (name "Net-(C49-Pad1)") (class "Default")
      (node (ref "C49") (pin "1") (pinfunction "1_1") (pintype "passive"))
      (node (ref "R77") (pin "2") (pinfunction "2_2") (pintype "passive"))
      (node (ref "R78") (pin "1") (pinfunction "1_1") (pintype "passive"))
    )
    (net (code "77") (name "Net-(C50-Pad1)") (class "Default")
      (node (ref "C50") (pin "1") (pinfunction "1_1") (pintype "passive"))
      (node (ref "R79") (pin "2") (pinfunction "2_2") (pintype "passive"))
      (node (ref "R80") (pin "1") (pinfunction "1_1") (pintype "passive"))
    )
    (net (code "78") (name "Net-(C51-Pad1)") (class "Default")
      (node (ref "C51") (pin "1") (pinfunction "1_1") (pintype "passive"))
      (node (ref "R81") (pin "2") (pinfunction "2_2") (pintype "passive"))
      (node (ref "R82") (pin "1") (pinfunction "1_1") (pintype "passive"))
    )
    (net (code "79") (name "Net-(C52-Pad1)") (class "Default")
      (node (ref "C52") (pin "1") (pinfunction "1_1") (pintype "passive"))
      (node (ref "R83") (pin "2") (pinfunction "2_2") (pintype "passive"))
      (node (ref "R84") (pin "1") (pinfunction "1_1") (pintype "passive"))
    )
    (net (code "80") (name "Net-(J1/J3-Analog_In-Pad26)") (class "Default")
      (node (ref "J1/J3") (pin "26") (pinfunction "Analog_In_26") (pintype "passive"))
      (node (ref "R58") (pin "1") (pinfunction "1_1") (pintype "passive"))
    )
    (net (code "81") (name "Net-(J1/J3-Analog_Out{slash}I2S_SDout)") (class "Default")
      (node (ref "J1/J3") (pin "29") (pinfunction "Analog_Out/I2S_SDout_29") (pintype "passive"))
      (node (ref "J15") (pin "2") (pinfunction "2_2") (pintype "passive"))
    )
    (net (code "82") (name "Net-(J1/J3-LP_UART_RX)") (class "Default")
      (node (ref "J1/J3") (pin "3") (pinfunction "LP_UART_RX_3") (pintype "passive"))
      (node (ref "J14") (pin "2") (pinfunction "2_2") (pintype "passive"))
    )
    (net (code "83") (name "Net-(J9-Pad2)") (class "Default")
      (node (ref "J9") (pin "2") (pinfunction "2_2") (pintype "passive"))
      (node (ref "R56") (pin "1") (pinfunction "1_1") (pintype "passive"))
      (node (ref "RT1") (pin "2") (pinfunction "2_2") (pintype "passive"))
    )
    (net (code "84") (name "Net-(J9-Pad3)") (class "Default")
      (node (ref "J9") (pin "3") (pinfunction "3_3") (pintype "passive"))
      (node (ref "R57") (pin "2") (pinfunction "2_2") (pintype "passive"))
    )
    (net (code "85") (name "Net-(U2A-IN_A-)") (class "Default")
      (node (ref "R70") (pin "2") (pinfunction "2_2") (pintype "passive"))
      (node (ref "R71") (pin "1") (pinfunction "1_1") (pintype "passive"))
      (node (ref "U2") (pin "2") (pinfunction "IN_A-_2") (pintype "input"))
    )
    (net (code "86") (name "Net-(U2A-VOUT_A)") (class "Default")
      (node (ref "R71") (pin "2") (pinfunction "2_2") (pintype "passive"))
      (node (ref "R73") (pin "1") (pinfunction "1_1") (pintype "passive"))
      (node (ref "U2") (pin "1") (pinfunction "VOUT_A_1") (pintype "output"))
    )
    (net (code "87") (name "Net-(U2B-IN_B+)") (class "Default")
      (node (ref "R73") (pin "2") (pinfunction "2_2") (pintype "passive"))
      (node (ref "U2") (pin "5") (pinfunction "IN_B+_5") (pintype "input"))
    )
    (net (code "88") (name "Net-(U2B-IN_B-)") (class "Default")
      (node (ref "R68") (pin "2") (pinfunction "2_2") (pintype "passive"))
      (node (ref "R69") (pin "1") (pinfunction "1_1") (pintype "passive"))
      (node (ref "U2") (pin "6") (pinfunction "IN_B-_6") (pintype "input"))
    )
    (net (code "89") (name "Net-(U2B-VOUT_B)") (class "Default")
      (node (ref "R69") (pin "2") (pinfunction "2_2") (pintype "passive"))
      (node (ref "R72") (pin "1") (pinfunction "1_1") (pintype "passive"))
      (node (ref "U2") (pin "7") (pinfunction "VOUT_B_7") (pintype "output"))
    )
  )
)
